# 7-InputSelect.net
KiCad netlist of a schematic drawn in EAGLE
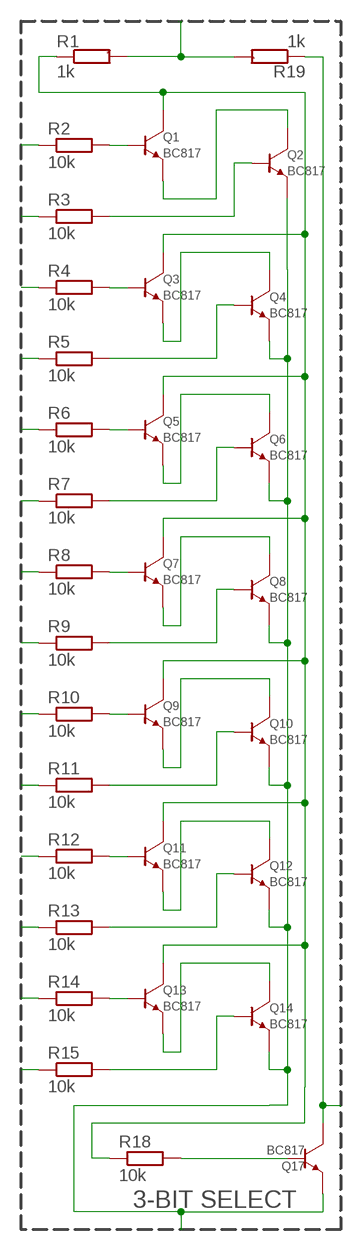
[diagram p0: schematic, sheet 1]

(export (version "E")
  (design (tool "Eeschema 10.0.6"))
  (components
    (comp (ref "Q1")
      (value "BC817")
      (footprint "eagle-import:SOT23")
      (libsource (lib "eagle-import") (part "TRANSISTOR-NPN-GENERIC-SOT23-BECDEFAULT"))
    )
    (comp (ref "Q2")
      (value "BC817")
      (footprint "eagle-import:SOT23")
      (libsource (lib "eagle-import") (part "TRANSISTOR-NPN-GENERIC-SOT23-BECDEFAULT"))
    )
    (comp (ref "Q3")
      (value "BC817")
      (footprint "eagle-import:SOT23")
      (libsource (lib "eagle-import") (part "TRANSISTOR-NPN-GENERIC-SOT23-BECDEFAULT"))
    )
    (comp (ref "Q4")
      (value "BC817")
      (footprint "eagle-import:SOT23")
      (libsource (lib "eagle-import") (part "TRANSISTOR-NPN-GENERIC-SOT23-BECDEFAULT"))
    )
    (comp (ref "Q5")
      (value "BC817")
      (footprint "eagle-import:SOT23")
      (libsource (lib "eagle-import") (part "TRANSISTOR-NPN-GENERIC-SOT23-BECDEFAULT"))
    )
    (comp (ref "Q6")
      (value "BC817")
      (footprint "eagle-import:SOT23")
      (libsource (lib "eagle-import") (part "TRANSISTOR-NPN-GENERIC-SOT23-BECDEFAULT"))
    )
    (comp (ref "Q7")
      (value "BC817")
      (footprint "eagle-import:SOT23")
      (libsource (lib "eagle-import") (part "TRANSISTOR-NPN-GENERIC-SOT23-BECDEFAULT"))
    )
    (comp (ref "Q8")
      (value "BC817")
      (footprint "eagle-import:SOT23")
      (libsource (lib "eagle-import") (part "TRANSISTOR-NPN-GENERIC-SOT23-BECDEFAULT"))
    )
    (comp (ref "Q9")
      (value "BC817")
      (footprint "eagle-import:SOT23")
      (libsource (lib "eagle-import") (part "TRANSISTOR-NPN-GENERIC-SOT23-BECDEFAULT"))
    )
    (comp (ref "Q10")
      (value "BC817")
      (footprint "eagle-import:SOT23")
      (libsource (lib "eagle-import") (part "TRANSISTOR-NPN-GENERIC-SOT23-BECDEFAULT"))
    )
    (comp (ref "Q11")
      (value "BC817")
      (footprint "eagle-import:SOT23")
      (libsource (lib "eagle-import") (part "TRANSISTOR-NPN-GENERIC-SOT23-BECDEFAULT"))
    )
    (comp (ref "Q12")
      (value "BC817")
      (footprint "eagle-import:SOT23")
      (libsource (lib "eagle-import") (part "TRANSISTOR-NPN-GENERIC-SOT23-BECDEFAULT"))
    )
    (comp (ref "Q13")
      (value "BC817")
      (footprint "eagle-import:SOT23")
      (libsource (lib "eagle-import") (part "TRANSISTOR-NPN-GENERIC-SOT23-BECDEFAULT"))
    )
    (comp (ref "Q14")
      (value "BC817")
      (footprint "eagle-import:SOT23")
      (libsource (lib "eagle-import") (part "TRANSISTOR-NPN-GENERIC-SOT23-BECDEFAULT"))
    )
    (comp (ref "Q17")
      (value "BC817")
      (footprint "eagle-import:SOT23")
      (libsource (lib "eagle-import") (part "TRANSISTOR-NPN-GENERIC-SOT23-BECDEFAULT"))
    )
    (comp (ref "R1")
      (value "1k")
      (footprint "eagle-import:R0603-MARK")
      (libsource (lib "eagle-import") (part "R-EU-MARKEDR0603"))
    )
    (comp (ref "R2")
      (value "10k")
      (footprint "eagle-import:R0603")
      (libsource (lib "eagle-import") (part "R-EU_R0603"))
    )
    (comp (ref "R3")
      (value "10k")
      (footprint "eagle-import:R0603")
      (libsource (lib "eagle-import") (part "R-EU_R0603"))
    )
    (comp (ref "R4")
      (value "10k")
      (footprint "eagle-import:R0603")
      (libsource (lib "eagle-import") (part "R-EU_R0603"))
    )
    (comp (ref "R5")
      (value "10k")
      (footprint "eagle-import:R0603")
      (libsource (lib "eagle-import") (part "R-EU_R0603"))
    )
    (comp (ref "R6")
      (value "10k")
      (footprint "eagle-import:R0603")
      (libsource (lib "eagle-import") (part "R-EU_R0603"))
    )
    (comp (ref "R7")
      (value "10k")
      (footprint "eagle-import:R0603")
      (libsource (lib "eagle-import") (part "R-EU_R0603"))
    )
    (comp (ref "R8")
      (value "10k")
      (footprint "eagle-import:R0603")
      (libsource (lib "eagle-import") (part "R-EU_R0603"))
    )
    (comp (ref "R9")
      (value "10k")
      (footprint "eagle-import:R0603")
      (libsource (lib "eagle-import") (part "R-EU_R0603"))
    )
    (comp (ref "R10")
      (value "10k")
      (footprint "eagle-import:R0603")
      (libsource (lib "eagle-import") (part "R-EU_R0603"))
    )
    (comp (ref "R11")
      (value "10k")
      (footprint "eagle-import:R0603")
      (libsource (lib "eagle-import") (part "R-EU_R0603"))
    )
    (comp (ref "R12")
      (value "10k")
      (footprint "eagle-import:R0603")
      (libsource (lib "eagle-import") (part "R-EU_R0603"))
    )
    (comp (ref "R13")
      (value "10k")
      (footprint "eagle-import:R0603")
      (libsource (lib "eagle-import") (part "R-EU_R0603"))
    )
    (comp (ref "R14")
      (value "10k")
      (footprint "eagle-import:R0603")
      (libsource (lib "eagle-import") (part "R-EU_R0603"))
    )
    (comp (ref "R15")
      (value "10k")
      (footprint "eagle-import:R0603")
      (libsource (lib "eagle-import") (part "R-EU_R0603"))
    )
    (comp (ref "R18")
      (value "10k")
      (footprint "eagle-import:R0603")
      (libsource (lib "eagle-import") (part "R-EU_R0603"))
    )
    (comp (ref "R19")
      (value "1k")
      (footprint "eagle-import:R0603-MARK")
      (libsource (lib "eagle-import") (part "R-EU-MARKEDR0603"))
    )
  )
  (nets
    (net (code "1") (name "Net-(Q1-BASE)") (class "Default")
      (node (ref "Q1") (pin "P$1") (pinfunction "BASE_P$1") (pintype "bidirectional"))
      (node (ref "R2") (pin "2") (pinfunction "2_2") (pintype "passive"))
    )
    (net (code "2") (name "Net-(Q1-COLLECTOR)") (class "Default")
      (node (ref "Q1") (pin "P$3") (pinfunction "COLLECTOR_P$3") (pintype "bidirectional"))
      (node (ref "Q11") (pin "P$3") (pinfunction "COLLECTOR_P$3") (pintype "bidirectional"))
      (node (ref "Q13") (pin "P$3") (pinfunction "COLLECTOR_P$3") (pintype "bidirectional"))
      (node (ref "Q3") (pin "P$3") (pinfunction "COLLECTOR_P$3") (pintype "bidirectional"))
      (node (ref "Q5") (pin "P$3") (pinfunction "COLLECTOR_P$3") (pintype "bidirectional"))
      (node (ref "Q7") (pin "P$3") (pinfunction "COLLECTOR_P$3") (pintype "bidirectional"))
      (node (ref "Q9") (pin "P$3") (pinfunction "COLLECTOR_P$3") (pintype "bidirectional"))
      (node (ref "R1") (pin "1") (pinfunction "1_1") (pintype "passive"))
      (node (ref "R18") (pin "1") (pinfunction "1_1") (pintype "passive"))
    )
    (net (code "3") (name "Net-(Q1-EMITTER)") (class "Default")
      (node (ref "Q1") (pin "P$2") (pinfunction "EMITTER_P$2") (pintype "bidirectional"))
      (node (ref "Q2") (pin "P$3") (pinfunction "COLLECTOR_P$3") (pintype "bidirectional"))
    )
    (net (code "4") (name "Net-(Q2-BASE)") (class "Default")
      (node (ref "Q2") (pin "P$1") (pinfunction "BASE_P$1") (pintype "bidirectional"))
      (node (ref "R3") (pin "2") (pinfunction "2_2") (pintype "passive"))
    )
    (net (code "5") (name "Net-(Q3-BASE)") (class "Default")
      (node (ref "Q3") (pin "P$1") (pinfunction "BASE_P$1") (pintype "bidirectional"))
      (node (ref "R4") (pin "2") (pinfunction "2_2") (pintype "passive"))
    )
    (net (code "6") (name "Net-(Q3-EMITTER)") (class "Default")
      (node (ref "Q3") (pin "P$2") (pinfunction "EMITTER_P$2") (pintype "bidirectional"))
      (node (ref "Q4") (pin "P$3") (pinfunction "COLLECTOR_P$3") (pintype "bidirectional"))
    )
    (net (code "7") (name "Net-(Q4-BASE)") (class "Default")
      (node (ref "Q4") (pin "P$1") (pinfunction "BASE_P$1") (pintype "bidirectional"))
      (node (ref "R5") (pin "2") (pinfunction "2_2") (pintype "passive"))
    )
    (net (code "8") (name "Net-(Q5-BASE)") (class "Default")
      (node (ref "Q5") (pin "P$1") (pinfunction "BASE_P$1") (pintype "bidirectional"))
      (node (ref "R6") (pin "2") (pinfunction "2_2") (pintype "passive"))
    )
    (net (code "9") (name "Net-(Q5-EMITTER)") (class "Default")
      (node (ref "Q5") (pin "P$2") (pinfunction "EMITTER_P$2") (pintype "bidirectional"))
      (node (ref "Q6") (pin "P$3") (pinfunction "COLLECTOR_P$3") (pintype "bidirectional"))
    )
    (net (code "10") (name "Net-(Q6-BASE)") (class "Default")
      (node (ref "Q6") (pin "P$1") (pinfunction "BASE_P$1") (pintype "bidirectional"))
      (node (ref "R7") (pin "2") (pinfunction "2_2") (pintype "passive"))
    )
    (net (code "11") (name "Net-(Q7-BASE)") (class "Default")
      (node (ref "Q7") (pin "P$1") (pinfunction "BASE_P$1") (pintype "bidirectional"))
      (node (ref "R8") (pin "2") (pinfunction "2_2") (pintype "passive"))
    )
    (net (code "12") (name "Net-(Q7-EMITTER)") (class "Default")
      (node (ref "Q7") (pin "P$2") (pinfunction "EMITTER_P$2") (pintype "bidirectional"))
      (node (ref "Q8") (pin "P$3") (pinfunction "COLLECTOR_P$3") (pintype "bidirectional"))
    )
    (net (code "13") (name "Net-(Q8-BASE)") (class "Default")
      (node (ref "Q8") (pin "P$1") (pinfunction "BASE_P$1") (pintype "bidirectional"))
      (node (ref "R9") (pin "2") (pinfunction "2_2") (pintype "passive"))
    )
    (net (code "14") (name "Net-(Q9-BASE)") (class "Default")
      (node (ref "Q9") (pin "P$1") (pinfunction "BASE_P$1") (pintype "bidirectional"))
      (node (ref "R10") (pin "2") (pinfunction "2_2") (pintype "passive"))
    )
    (net (code "15") (name "Net-(Q10-BASE)") (class "Default")
      (node (ref "Q10") (pin "P$1") (pinfunction "BASE_P$1") (pintype "bidirectional"))
      (node (ref "R11") (pin "2") (pinfunction "2_2") (pintype "passive"))
    )
    (net (code "16") (name "Net-(Q10-COLLECTOR)") (class "Default")
      (node (ref "Q10") (pin "P$3") (pinfunction "COLLECTOR_P$3") (pintype "bidirectional"))
      (node (ref "Q9") (pin "P$2") (pinfunction "EMITTER_P$2") (pintype "bidirectional"))
    )
    (net (code "17") (name "Net-(Q10-EMITTER)") (class "Default")
      (node (ref "Q10") (pin "P$2") (pinfunction "EMITTER_P$2") (pintype "bidirectional"))
      (node (ref "Q12") (pin "P$2") (pinfunction "EMITTER_P$2") (pintype "bidirectional"))
      (node (ref "Q14") (pin "P$2") (pinfunction "EMITTER_P$2") (pintype "bidirectional"))
      (node (ref "Q17") (pin "P$2") (pinfunction "EMITTER_P$2") (pintype "bidirectional"))
      (node (ref "Q2") (pin "P$2") (pinfunction "EMITTER_P$2") (pintype "bidirectional"))
      (node (ref "Q4") (pin "P$2") (pinfunction "EMITTER_P$2") (pintype "bidirectional"))
      (node (ref "Q6") (pin "P$2") (pinfunction "EMITTER_P$2") (pintype "bidirectional"))
      (node (ref "Q8") (pin "P$2") (pinfunction "EMITTER_P$2") (pintype "bidirectional"))
    )
    (net (code "18") (name "Net-(Q11-BASE)") (class "Default")
      (node (ref "Q11") (pin "P$1") (pinfunction "BASE_P$1") (pintype "bidirectional"))
      (node (ref "R12") (pin "2") (pinfunction "2_2") (pintype "passive"))
    )
    (net (code "19") (name "Net-(Q11-EMITTER)") (class "Default")
      (node (ref "Q11") (pin "P$2") (pinfunction "EMITTER_P$2") (pintype "bidirectional"))
      (node (ref "Q12") (pin "P$3") (pinfunction "COLLECTOR_P$3") (pintype "bidirectional"))
    )
    (net (code "20") (name "Net-(Q12-BASE)") (class "Default")
      (node (ref "Q12") (pin "P$1") (pinfunction "BASE_P$1") (pintype "bidirectional"))
      (node (ref "R13") (pin "2") (pinfunction "2_2") (pintype "passive"))
    )
    (net (code "21") (name "Net-(Q13-BASE)") (class "Default")
      (node (ref "Q13") (pin "P$1") (pinfunction "BASE_P$1") (pintype "bidirectional"))
      (node (ref "R14") (pin "2") (pinfunction "2_2") (pintype "passive"))
    )
    (net (code "22") (name "Net-(Q13-EMITTER)") (class "Default")
      (node (ref "Q13") (pin "P$2") (pinfunction "EMITTER_P$2") (pintype "bidirectional"))
      (node (ref "Q14") (pin "P$3") (pinfunction "COLLECTOR_P$3") (pintype "bidirectional"))
    )
    (net (code "23") (name "Net-(Q14-BASE)") (class "Default")
      (node (ref "Q14") (pin "P$1") (pinfunction "BASE_P$1") (pintype "bidirectional"))
      (node (ref "R15") (pin "2") (pinfunction "2_2") (pintype "passive"))
    )
    (net (code "24") (name "Net-(Q17-BASE)") (class "Default")
      (node (ref "Q17") (pin "P$1") (pinfunction "BASE_P$1") (pintype "bidirectional"))
      (node (ref "R18") (pin "2") (pinfunction "2_2") (pintype "passive"))
    )
    (net (code "25") (name "Net-(Q17-COLLECTOR)") (class "Default")
      (node (ref "Q17") (pin "P$3") (pinfunction "COLLECTOR_P$3") (pintype "bidirectional"))
      (node (ref "R19") (pin "1") (pinfunction "1_1") (pintype "passive"))
    )
    (net (code "26") (name "Net-(R1-Pad2)") (class "Default")
      (node (ref "R1") (pin "2") (pinfunction "2_2") (pintype "passive"))
      (node (ref "R19") (pin "2") (pinfunction "2_2") (pintype "passive"))
    )
    (net (code "27") (name "unconnected-(R2-Pad1)") (class "Default")
      (node (ref "R2") (pin "1") (pinfunction "1_1") (pintype "passive"))
    )
    (net (code "28") (name "unconnected-(R3-Pad1)") (class "Default")
      (node (ref "R3") (pin "1") (pinfunction "1_1") (pintype "passive"))
    )
    (net (code "29") (name "unconnected-(R4-Pad1)") (class "Default")
      (node (ref "R4") (pin "1") (pinfunction "1_1") (pintype "passive"))
    )
    (net (code "30") (name "unconnected-(R5-Pad1)") (class "Default")
      (node (ref "R5") (pin "1") (pinfunction "1_1") (pintype "passive"))
    )
    (net (code "31") (name "unconnected-(R6-Pad1)") (class "Default")
      (node (ref "R6") (pin "1") (pinfunction "1_1") (pintype "passive"))
    )
    (net (code "32") (name "unconnected-(R7-Pad1)") (class "Default")
      (node (ref "R7") (pin "1") (pinfunction "1_1") (pintype "passive"))
    )
    (net (code "33") (name "unconnected-(R8-Pad1)") (class "Default")
      (node (ref "R8") (pin "1") (pinfunction "1_1") (pintype "passive"))
    )
    (net (code "34") (name "unconnected-(R9-Pad1)") (class "Default")
      (node (ref "R9") (pin "1") (pinfunction "1_1") (pintype "passive"))
    )
    (net (code "35") (name "unconnected-(R10-Pad1)") (class "Default")
      (node (ref "R10") (pin "1") (pinfunction "1_1") (pintype "passive"))
    )
    (net (code "36") (name "unconnected-(R11-Pad1)") (class "Default")
      (node (ref "R11") (pin "1") (pinfunction "1_1") (pintype "passive"))
    )
    (net (code "37") (name "unconnected-(R12-Pad1)") (class "Default")
      (node (ref "R12") (pin "1") (pinfunction "1_1") (pintype "passive"))
    )
    (net (code "38") (name "unconnected-(R13-Pad1)") (class "Default")
      (node (ref "R13") (pin "1") (pinfunction "1_1") (pintype "passive"))
    )
    (net (code "39") (name "unconnected-(R14-Pad1)") (class "Default")
      (node (ref "R14") (pin "1") (pinfunction "1_1") (pintype "passive"))
    )
    (net (code "40") (name "unconnected-(R15-Pad1)") (class "Default")
      (node (ref "R15") (pin "1") (pinfunction "1_1") (pintype "passive"))
    )
  )
)
